# ComponentCounterLeds.net
KiCad netlist of a schematic drawn in EAGLE
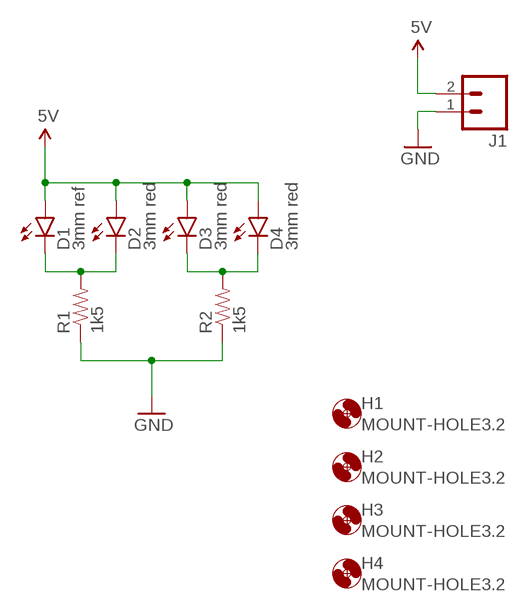
[diagram p0: schematic, sheet 1]

(export (version "E")
  (design (tool "Eeschema 10.0.6"))
  (components
    (comp (ref "D1")
      (value "3mm ref")
      (footprint "eagle-import:LED3MM-NS")
      (libsource (lib "eagle-import") (part "LED-3MM-NO_SILK"))
    )
    (comp (ref "D2")
      (value "3mm red")
      (footprint "eagle-import:LED3MM-NS")
      (libsource (lib "eagle-import") (part "LED-3MM-NO_SILK"))
    )
    (comp (ref "D3")
      (value "3mm red")
      (footprint "eagle-import:LED3MM-NS")
      (libsource (lib "eagle-import") (part "LED-3MM-NO_SILK"))
    )
    (comp (ref "D4")
      (value "3mm red")
      (footprint "eagle-import:LED3MM-NS")
      (libsource (lib "eagle-import") (part "LED-3MM-NO_SILK"))
    )
    (comp (ref "H1")
      (value "MOUNT-HOLE3.2")
      (footprint "eagle-import:3,2")
      (libsource (lib "eagle-import") (part "MOUNT-HOLE3.2"))
    )
    (comp (ref "H2")
      (value "MOUNT-HOLE3.2")
      (footprint "eagle-import:3,2")
      (libsource (lib "eagle-import") (part "MOUNT-HOLE3.2"))
    )
    (comp (ref "H3")
      (value "MOUNT-HOLE3.2")
      (footprint "eagle-import:3,2")
      (libsource (lib "eagle-import") (part "MOUNT-HOLE3.2"))
    )
    (comp (ref "H4")
      (value "MOUNT-HOLE3.2")
      (footprint "eagle-import:3,2")
      (libsource (lib "eagle-import") (part "MOUNT-HOLE3.2"))
    )
    (comp (ref "J1")
      (value "M02-JST-2MM-SMT")
      (footprint "eagle-import:JST-2-SMD")
      (libsource (lib "eagle-import") (part "M02-JST-2MM-SMT"))
    )
    (comp (ref "R1")
      (value "1k5")
      (footprint "eagle-import:1206")
      (libsource (lib "eagle-import") (part "RESISTOR1206"))
    )
    (comp (ref "R2")
      (value "1k5")
      (footprint "eagle-import:1206")
      (libsource (lib "eagle-import") (part "RESISTOR1206"))
    )
  )
  (nets
    (net (code "1") (name "5V") (class "Default")
      (node (ref "D1") (pin "A") (pinfunction "A_A") (pintype "passive"))
      (node (ref "D2") (pin "A") (pinfunction "A_A") (pintype "passive"))
      (node (ref "D3") (pin "A") (pinfunction "A_A") (pintype "passive"))
      (node (ref "D4") (pin "A") (pinfunction "A_A") (pintype "passive"))
      (node (ref "J1") (pin "2") (pinfunction "1_2") (pintype "passive"))
    )
    (net (code "2") (name "GND") (class "Default")
      (node (ref "J1") (pin "1") (pinfunction "2_1") (pintype "passive"))
      (node (ref "R1") (pin "1") (pinfunction "1_1") (pintype "passive"))
      (node (ref "R2") (pin "1") (pinfunction "1_1") (pintype "passive"))
    )
    (net (code "3") (name "Net-(D1-C)") (class "Default")
      (node (ref "D1") (pin "K") (pinfunction "C_K") (pintype "passive"))
      (node (ref "D2") (pin "K") (pinfunction "C_K") (pintype "passive"))
      (node (ref "R1") (pin "2") (pinfunction "2_2") (pintype "passive"))
    )
    (net (code "4") (name "Net-(D3-C)") (class "Default")
      (node (ref "D3") (pin "K") (pinfunction "C_K") (pintype "passive"))
      (node (ref "D4") (pin "K") (pinfunction "C_K") (pintype "passive"))
      (node (ref "R2") (pin "2") (pinfunction "2_2") (pintype "passive"))
    )
  )
)
